# PowerCommConnector.net
KiCad netlist of a schematic drawn in Altium Designer
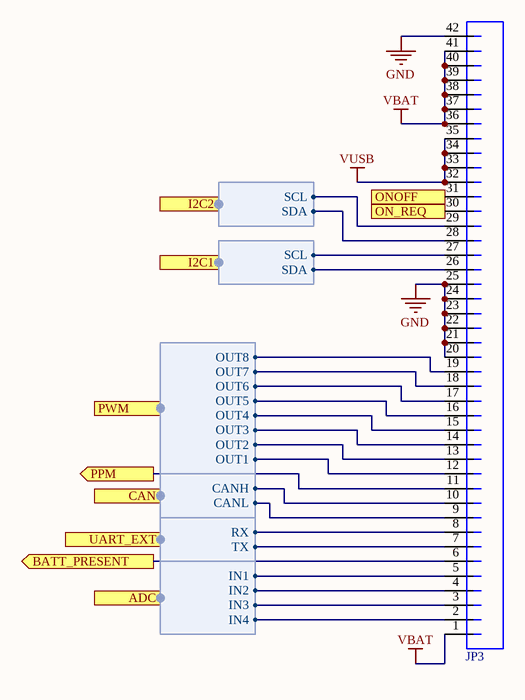
[diagram p0: PowerCommConnector.SchDoc]

(export (version "E")
  (design (tool "Eeschema 10.0.6"))
  (components
    (comp (ref "JP3")
      (value "HIROSE_BM23PF_40_RECEPTACLE")
      (footprint "HIROSE-BM23PF-40-0.35MM-RECEPTACLE")
      (description "CONN RCPT 0.35MM SMD 40POS")
      (fields (field (name "MANUFACTURER") "Hirose") (field (name "PARTNUMBER") "BM23PF0.8-40DS-0.35V(51)"))
      (libsource (lib "Connectors") (part "HIROSE_BM23PF_40_RECEPTACLE"))
    )
  )
  (nets
    (net (code "6") (name "/BATT_PRESENT") (class "Default")
      (node (ref "JP3") (pin "6") (pinfunction "6_6") (pintype "passive"))
    )
    (net (code "7") (name "/ONOFF") (class "Default")
      (node (ref "JP3") (pin "31") (pinfunction "31_31") (pintype "passive"))
    )
    (net (code "8") (name "/ON_REQ") (class "Default")
      (node (ref "JP3") (pin "30") (pinfunction "30_30") (pintype "passive"))
    )
    (net (code "9") (name "/PPM") (class "Default")
      (node (ref "JP3") (pin "11") (pinfunction "11_11") (pintype "passive"))
    )
    (net (code "15") (name "GND") (class "Default")
      (node (ref "JP3") (pin "20") (pinfunction "20_20") (pintype "passive"))
      (node (ref "JP3") (pin "21") (pinfunction "21_21") (pintype "passive"))
      (node (ref "JP3") (pin "22") (pinfunction "22_22") (pintype "passive"))
      (node (ref "JP3") (pin "23") (pinfunction "23_23") (pintype "passive"))
      (node (ref "JP3") (pin "24") (pinfunction "24_24") (pintype "passive"))
      (node (ref "JP3") (pin "25") (pinfunction "25_25") (pintype "passive"))
      (node (ref "JP3") (pin "42") (pinfunction "42_42") (pintype "passive"))
    )
    (net (code "16") (name "VBAT") (class "Default")
      (node (ref "JP3") (pin "1") (pinfunction "1_1") (pintype "passive"))
      (node (ref "JP3") (pin "36") (pinfunction "36_36") (pintype "passive"))
      (node (ref "JP3") (pin "37") (pinfunction "37_37") (pintype "passive"))
      (node (ref "JP3") (pin "38") (pinfunction "38_38") (pintype "passive"))
      (node (ref "JP3") (pin "39") (pinfunction "39_39") (pintype "passive"))
      (node (ref "JP3") (pin "40") (pinfunction "40_40") (pintype "passive"))
      (node (ref "JP3") (pin "41") (pinfunction "41_41") (pintype "passive"))
    )
    (net (code "17") (name "VUSB") (class "Default")
      (node (ref "JP3") (pin "32") (pinfunction "32_32") (pintype "passive"))
      (node (ref "JP3") (pin "33") (pinfunction "33_33") (pintype "passive"))
      (node (ref "JP3") (pin "34") (pinfunction "34_34") (pintype "passive"))
      (node (ref "JP3") (pin "35") (pinfunction "35_35") (pintype "passive"))
    )
    (net (code "18") (name "unconnected-(JP3-Pad2)") (class "Default")
      (node (ref "JP3") (pin "2") (pinfunction "2_2") (pintype "passive"))
    )
    (net (code "19") (name "unconnected-(JP3-Pad3)") (class "Default")
      (node (ref "JP3") (pin "3") (pinfunction "3_3") (pintype "passive"))
    )
    (net (code "20") (name "unconnected-(JP3-Pad4)") (class "Default")
      (node (ref "JP3") (pin "4") (pinfunction "4_4") (pintype "passive"))
    )
    (net (code "21") (name "unconnected-(JP3-Pad5)") (class "Default")
      (node (ref "JP3") (pin "5") (pinfunction "5_5") (pintype "passive"))
    )
    (net (code "22") (name "unconnected-(JP3-Pad7)") (class "Default")
      (node (ref "JP3") (pin "7") (pinfunction "7_7") (pintype "passive"))
    )
    (net (code "23") (name "unconnected-(JP3-Pad8)") (class "Default")
      (node (ref "JP3") (pin "8") (pinfunction "8_8") (pintype "passive"))
    )
    (net (code "24") (name "unconnected-(JP3-Pad9)") (class "Default")
      (node (ref "JP3") (pin "9") (pinfunction "9_9") (pintype "passive"))
    )
    (net (code "25") (name "unconnected-(JP3-Pad10)") (class "Default")
      (node (ref "JP3") (pin "10") (pinfunction "10_10") (pintype "passive"))
    )
    (net (code "26") (name "unconnected-(JP3-Pad12)") (class "Default")
      (node (ref "JP3") (pin "12") (pinfunction "12_12") (pintype "passive"))
    )
    (net (code "27") (name "unconnected-(JP3-Pad13)") (class "Default")
      (node (ref "JP3") (pin "13") (pinfunction "13_13") (pintype "passive"))
    )
    (net (code "28") (name "unconnected-(JP3-Pad14)") (class "Default")
      (node (ref "JP3") (pin "14") (pinfunction "14_14") (pintype "passive"))
    )
    (net (code "29") (name "unconnected-(JP3-Pad15)") (class "Default")
      (node (ref "JP3") (pin "15") (pinfunction "15_15") (pintype "passive"))
    )
    (net (code "30") (name "unconnected-(JP3-Pad16)") (class "Default")
      (node (ref "JP3") (pin "16") (pinfunction "16_16") (pintype "passive"))
    )
    (net (code "31") (name "unconnected-(JP3-Pad17)") (class "Default")
      (node (ref "JP3") (pin "17") (pinfunction "17_17") (pintype "passive"))
    )
    (net (code "32") (name "unconnected-(JP3-Pad18)") (class "Default")
      (node (ref "JP3") (pin "18") (pinfunction "18_18") (pintype "passive"))
    )
    (net (code "33") (name "unconnected-(JP3-Pad19)") (class "Default")
      (node (ref "JP3") (pin "19") (pinfunction "19_19") (pintype "passive"))
    )
    (net (code "34") (name "unconnected-(JP3-Pad26)") (class "Default")
      (node (ref "JP3") (pin "26") (pinfunction "26_26") (pintype "passive"))
    )
    (net (code "35") (name "unconnected-(JP3-Pad27)") (class "Default")
      (node (ref "JP3") (pin "27") (pinfunction "27_27") (pintype "passive"))
    )
    (net (code "36") (name "unconnected-(JP3-Pad28)") (class "Default")
      (node (ref "JP3") (pin "28") (pinfunction "28_28") (pintype "passive"))
    )
    (net (code "37") (name "unconnected-(JP3-Pad29)") (class "Default")
      (node (ref "JP3") (pin "29") (pinfunction "29_29") (pintype "passive"))
    )
  )
)
